# 02_-ESP8266.net
KiCad netlist of a schematic drawn in Altium Designer
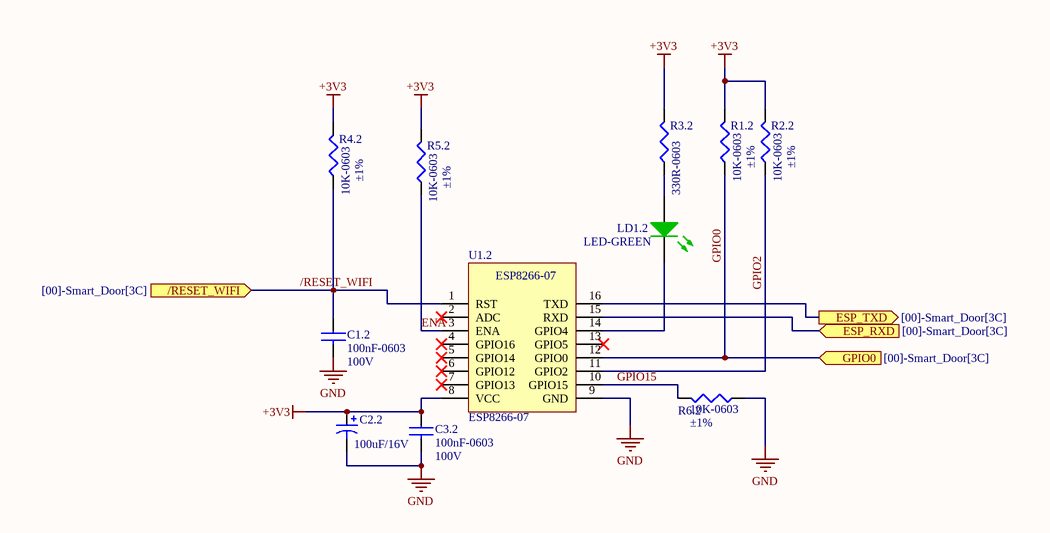
[diagram p0: [02]-ESP8266.SchDoc]

(export (version "E")
  (design (tool "Eeschema 10.0.6"))
  (components
    (comp (ref "C1.2")
      (value "100nF-0603")
      (footprint "CAP0603")
      (description "CAP CER 0.1UF 100V X7R 0603")
      (fields
        (field (name "MANUFACTURER") "Yageo")
        (field (name "MANUFACTURER PART NUMBER") "CC0603KRX7R0BB104")
        (field (name "VOLTAGE - RATED") "100V")
      )
      (libsource (lib "Indruino") (part "CC0603KRX7R0BB104"))
    )
    (comp (ref "C2.2")
      (value "100uF/16V")
      (footprint "MinhTien_PcbLib:CAPPR5-13x20")
      (description "Polarized Capacitor")
      (fields (field (name "PUBLISHER") "Altium Limited"))
      (libsource (lib "MinhTien_SCHLib") (part "Cap Polar"))
    )
    (comp (ref "C3.2")
      (value "100nF-0603")
      (footprint "CAP0603")
      (description "CAP CER 0.1UF 100V X7R 0603")
      (fields
        (field (name "MANUFACTURER") "Yageo")
        (field (name "MANUFACTURER PART NUMBER") "CC0603KRX7R0BB104")
        (field (name "VOLTAGE - RATED") "100V")
      )
      (libsource (lib "Indruino") (part "CC0603KRX7R0BB104"))
    )
    (comp (ref "LD1.2")
      (value "LED-GREEN")
      (footprint "Indruino:LED_SMD0603_GREEN")
      (description "LED GREEN CLEAR 0603 SMD")
      (libsource (lib "Indruino") (part "LED_LTST-C191KGKT"))
    )
    (comp (ref "R1.2")
      (value "10K-0603")
      (footprint "RES0603")
      (description "RES SMD 10K OHM 1% 1/10W 0603")
      (fields
        (field (name "MANUFACTURER") "Yageo")
        (field (name "MANUFACTURER PART NUMBER") "RC0603FR-0710KL")
        (field (name "TOLERANCE") "±1%")
      )
      (libsource (lib "Indruino") (part "RC0603FR-0710KL"))
    )
    (comp (ref "R2.2")
      (value "10K-0603")
      (footprint "RES0603")
      (description "RES SMD 10K OHM 1% 1/10W 0603")
      (fields
        (field (name "MANUFACTURER") "Yageo")
        (field (name "MANUFACTURER PART NUMBER") "RC0603FR-0710KL")
        (field (name "TOLERANCE") "±1%")
      )
      (libsource (lib "Indruino") (part "RC0603FR-0710KL"))
    )
    (comp (ref "R3.2")
      (value "330R-0603")
      (footprint "RES0603")
      (description "RES SMD 330 OHM 5% 1/10W 0603")
      (fields (field (name "TOLERANCE") "±5%"))
      (libsource (lib "Indruino") (part "RC0603JR-07330RL"))
    )
    (comp (ref "R4.2")
      (value "10K-0603")
      (footprint "RES0603")
      (description "RES SMD 10K OHM 1% 1/10W 0603")
      (fields
        (field (name "MANUFACTURER") "Yageo")
        (field (name "MANUFACTURER PART NUMBER") "RC0603FR-0710KL")
        (field (name "TOLERANCE") "±1%")
      )
      (libsource (lib "Indruino") (part "RC0603FR-0710KL"))
    )
    (comp (ref "R5.2")
      (value "10K-0603")
      (footprint "RES0603")
      (description "RES SMD 10K OHM 1% 1/10W 0603")
      (fields
        (field (name "MANUFACTURER") "Yageo")
        (field (name "MANUFACTURER PART NUMBER") "RC0603FR-0710KL")
        (field (name "TOLERANCE") "±1%")
      )
      (libsource (lib "Indruino") (part "RC0603FR-0710KL"))
    )
    (comp (ref "R6.2")
      (value "10K-0603")
      (footprint "RES0603")
      (description "RES SMD 10K OHM 1% 1/10W 0603")
      (fields
        (field (name "MANUFACTURER") "Yageo")
        (field (name "MANUFACTURER PART NUMBER") "RC0603FR-0710KL")
        (field (name "TOLERANCE") "±1%")
      )
      (libsource (lib "Indruino") (part "RC0603FR-0710KL"))
    )
    (comp (ref "U1.2")
      (value "ESP8266-07")
      (footprint "AZ_Lib:ESP8266-07_MODULE")
      (description "WIFI ESP8266 07")
      (libsource (lib "AZ_Lib") (part "ESP8266-07"))
    )
  )
  (nets
    (net (code "1") (name "+3V3") (class "Default")
      (node (ref "C2.2") (pin "1") (pinfunction "1_1") (pintype "passive"))
      (node (ref "C3.2") (pin "1") (pinfunction "1_1") (pintype "passive"))
      (node (ref "R1.2") (pin "2") (pinfunction "2_2") (pintype "passive"))
      (node (ref "R2.2") (pin "2") (pinfunction "2_2") (pintype "passive"))
      (node (ref "R3.2") (pin "2") (pinfunction "2_2") (pintype "passive"))
      (node (ref "R4.2") (pin "2") (pinfunction "2_2") (pintype "passive"))
      (node (ref "R5.2") (pin "2") (pinfunction "2_2") (pintype "passive"))
      (node (ref "U1.2") (pin "8") (pinfunction "VCC_8") (pintype "passive"))
    )
    (net (code "2") (name "/ENA") (class "Default")
      (node (ref "R5.2") (pin "1") (pinfunction "1_1") (pintype "passive"))
      (node (ref "U1.2") (pin "3") (pinfunction "ENA_3") (pintype "passive"))
    )
    (net (code "3") (name "/ESP_RXD") (class "Default")
      (node (ref "U1.2") (pin "15") (pinfunction "RXD_15") (pintype "passive"))
    )
    (net (code "4") (name "/ESP_TXD") (class "Default")
      (node (ref "U1.2") (pin "16") (pinfunction "TXD_16") (pintype "passive"))
    )
    (net (code "5") (name "/GPIO0") (class "Default")
      (node (ref "R1.2") (pin "1") (pinfunction "1_1") (pintype "passive"))
      (node (ref "U1.2") (pin "12") (pinfunction "GPIO0_12") (pintype "passive"))
    )
    (net (code "6") (name "/GPIO2") (class "Default")
      (node (ref "R2.2") (pin "1") (pinfunction "1_1") (pintype "passive"))
      (node (ref "U1.2") (pin "11") (pinfunction "GPIO2_11") (pintype "passive"))
    )
    (net (code "7") (name "/GPIO15") (class "Default")
      (node (ref "R6.2") (pin "2") (pinfunction "2_2") (pintype "passive"))
      (node (ref "U1.2") (pin "10") (pinfunction "GPIO15_10") (pintype "passive"))
    )
    (net (code "8") (name "/{slash}RESET_WIFI") (class "Default")
      (node (ref "C1.2") (pin "1") (pinfunction "1_1") (pintype "passive"))
      (node (ref "R4.2") (pin "1") (pinfunction "1_1") (pintype "passive"))
      (node (ref "U1.2") (pin "1") (pinfunction "RST_1") (pintype "passive"))
    )
    (net (code "9") (name "GND") (class "Default")
      (node (ref "C1.2") (pin "2") (pinfunction "2_2") (pintype "passive"))
      (node (ref "C2.2") (pin "2") (pinfunction "2_2") (pintype "passive"))
      (node (ref "C3.2") (pin "2") (pinfunction "2_2") (pintype "passive"))
      (node (ref "R6.2") (pin "1") (pinfunction "1_1") (pintype "passive"))
      (node (ref "U1.2") (pin "9") (pinfunction "GND_9") (pintype "passive"))
    )
    (net (code "10") (name "Net-(LD1.2-A)") (class "Default")
      (node (ref "LD1.2") (pin "1") (pinfunction "A_1") (pintype "passive"))
      (node (ref "R3.2") (pin "1") (pinfunction "1_1") (pintype "passive"))
    )
    (net (code "11") (name "Net-(LD1.2-K)") (class "Default")
      (node (ref "LD1.2") (pin "2") (pinfunction "K_2") (pintype "passive"))
      (node (ref "U1.2") (pin "14") (pinfunction "GPIO4_14") (pintype "passive"))
    )
    (net (code "12") (name "unconnected-(U1.2-ADC-Pad2)") (class "Default")
      (node (ref "U1.2") (pin "2") (pinfunction "ADC_2") (pintype "passive+no_connect"))
    )
    (net (code "13") (name "unconnected-(U1.2-GPIO5-Pad13)") (class "Default")
      (node (ref "U1.2") (pin "13") (pinfunction "GPIO5_13") (pintype "passive+no_connect"))
    )
    (net (code "14") (name "unconnected-(U1.2-GPIO12-Pad6)") (class "Default")
      (node (ref "U1.2") (pin "6") (pinfunction "GPIO12_6") (pintype "passive+no_connect"))
    )
    (net (code "15") (name "unconnected-(U1.2-GPIO13-Pad7)") (class "Default")
      (node (ref "U1.2") (pin "7") (pinfunction "GPIO13_7") (pintype "passive+no_connect"))
    )
    (net (code "16") (name "unconnected-(U1.2-GPIO14-Pad5)") (class "Default")
      (node (ref "U1.2") (pin "5") (pinfunction "GPIO14_5") (pintype "passive+no_connect"))
    )
    (net (code "17") (name "unconnected-(U1.2-GPIO16-Pad4)") (class "Default")
      (node (ref "U1.2") (pin "4") (pinfunction "GPIO16_4") (pintype "passive+no_connect"))
    )
  )
)
